# display.net
KiCad netlist of a schematic drawn in EAGLE
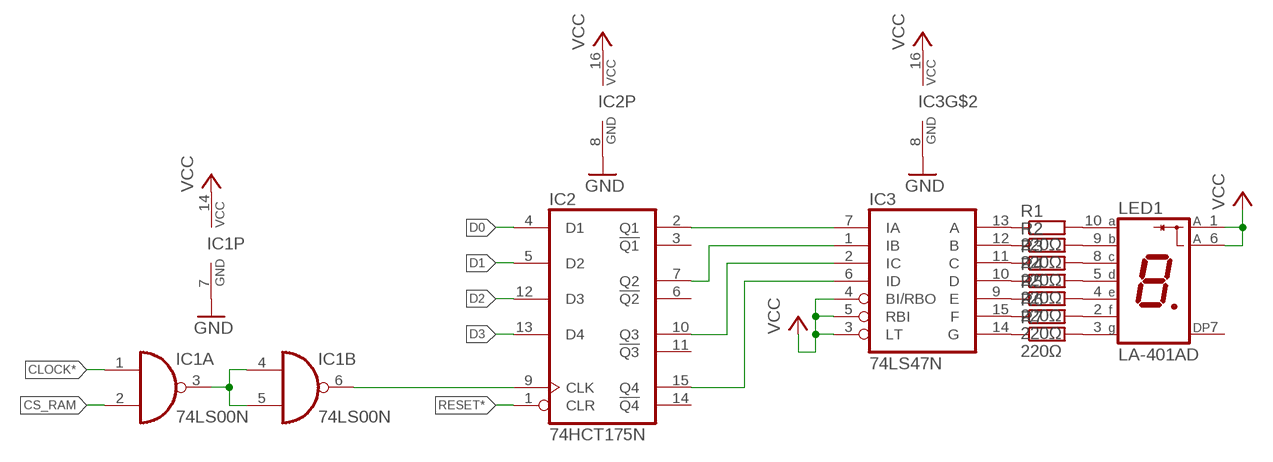
[diagram p0: schematic, sheet 1]

(export (version "E")
  (design (tool "Eeschema 10.0.6"))
  (components
    (comp (ref "IC1")
      (value "74LS00N")
      (footprint "eagle-import:DIL14")
      (libsource (lib "eagle-import") (part "7400NLS"))
    )
    (comp (ref "IC2")
      (value "74HCT175N")
      (footprint "eagle-import:DIL16")
      (libsource (lib "eagle-import") (part "74175NHCT"))
    )
    (comp (ref "IC3")
      (value "74LS47N")
      (footprint "eagle-import:DIL16")
      (libsource (lib "eagle-import") (part "7447NLS"))
    )
    (comp (ref "LED1")
      (value "LA-401AD")
      (footprint "eagle-import:LA-401")
      (libsource (lib "eagle-import") (part "LA-401DA"))
    )
    (comp (ref "R1")
      (value "220Ω")
      (footprint "eagle-import:0207_10")
      (libsource (lib "eagle-import") (part "R-EU_0207/10"))
    )
    (comp (ref "R2")
      (value "220Ω")
      (footprint "eagle-import:0207_10")
      (libsource (lib "eagle-import") (part "R-EU_0207/10"))
    )
    (comp (ref "R3")
      (value "220Ω")
      (footprint "eagle-import:0207_10")
      (libsource (lib "eagle-import") (part "R-EU_0207/10"))
    )
    (comp (ref "R4")
      (value "220Ω")
      (footprint "eagle-import:0207_10")
      (libsource (lib "eagle-import") (part "R-EU_0207/10"))
    )
    (comp (ref "R5")
      (value "220Ω")
      (footprint "eagle-import:0207_10")
      (libsource (lib "eagle-import") (part "R-EU_0207/10"))
    )
    (comp (ref "R6")
      (value "220Ω")
      (footprint "eagle-import:0207_10")
      (libsource (lib "eagle-import") (part "R-EU_0207/10"))
    )
    (comp (ref "R7")
      (value "220Ω")
      (footprint "eagle-import:0207_10")
      (libsource (lib "eagle-import") (part "R-EU_0207/10"))
    )
  )
  (nets
    (net (code "1") (name "CLOCK*") (class "Default")
      (node (ref "IC1") (pin "1") (pinfunction "I0_1") (pintype "input"))
    )
    (net (code "2") (name "CS_RAM") (class "Default")
      (node (ref "IC1") (pin "2") (pinfunction "I1_2") (pintype "input"))
    )
    (net (code "3") (name "D0") (class "Default")
      (node (ref "IC2") (pin "4") (pinfunction "D1_4") (pintype "input"))
    )
    (net (code "4") (name "D1") (class "Default")
      (node (ref "IC2") (pin "5") (pinfunction "D2_5") (pintype "input"))
    )
    (net (code "5") (name "D2") (class "Default")
      (node (ref "IC2") (pin "12") (pinfunction "D3_12") (pintype "input"))
    )
    (net (code "6") (name "D3") (class "Default")
      (node (ref "IC2") (pin "13") (pinfunction "D4_13") (pintype "input"))
    )
    (net (code "7") (name "GND") (class "Default")
      (node (ref "IC1") (pin "7") (pinfunction "GND_7") (pintype "power_in"))
      (node (ref "IC2") (pin "8") (pinfunction "GND_8") (pintype "power_in"))
      (node (ref "IC3") (pin "8") (pinfunction "GND_8") (pintype "power_in"))
    )
    (net (code "8") (name "Net-(IC1A-O)") (class "Default")
      (node (ref "IC1") (pin "3") (pinfunction "O_3") (pintype "output"))
      (node (ref "IC1") (pin "4") (pinfunction "I0_4") (pintype "input"))
      (node (ref "IC1") (pin "5") (pinfunction "I1_5") (pintype "input"))
    )
    (net (code "9") (name "Net-(IC1B-O)") (class "Default")
      (node (ref "IC1") (pin "6") (pinfunction "O_6") (pintype "output"))
      (node (ref "IC2") (pin "9") (pinfunction "CLK_9") (pintype "input"))
    )
    (net (code "10") (name "Net-(IC2A-Q1)") (class "Default")
      (node (ref "IC2") (pin "2") (pinfunction "Q1_2") (pintype "output"))
      (node (ref "IC3") (pin "7") (pinfunction "IA_7") (pintype "input"))
    )
    (net (code "11") (name "Net-(IC2A-Q2)") (class "Default")
      (node (ref "IC2") (pin "7") (pinfunction "Q2_7") (pintype "output"))
      (node (ref "IC3") (pin "1") (pinfunction "IB_1") (pintype "input"))
    )
    (net (code "12") (name "Net-(IC2A-Q3)") (class "Default")
      (node (ref "IC2") (pin "10") (pinfunction "Q3_10") (pintype "output"))
      (node (ref "IC3") (pin "2") (pinfunction "IC_2") (pintype "input"))
    )
    (net (code "13") (name "Net-(IC2A-Q4)") (class "Default")
      (node (ref "IC2") (pin "15") (pinfunction "Q4_15") (pintype "output"))
      (node (ref "IC3") (pin "6") (pinfunction "ID_6") (pintype "input"))
    )
    (net (code "14") (name "Net-(IC3A-A)") (class "Default")
      (node (ref "IC3") (pin "13") (pinfunction "A_13") (pintype "output"))
      (node (ref "R1") (pin "1") (pinfunction "1_1") (pintype "passive"))
    )
    (net (code "15") (name "Net-(IC3A-B)") (class "Default")
      (node (ref "IC3") (pin "12") (pinfunction "B_12") (pintype "output"))
      (node (ref "R2") (pin "1") (pinfunction "1_1") (pintype "passive"))
    )
    (net (code "16") (name "Net-(IC3A-C)") (class "Default")
      (node (ref "IC3") (pin "11") (pinfunction "C_11") (pintype "output"))
      (node (ref "R3") (pin "1") (pinfunction "1_1") (pintype "passive"))
    )
    (net (code "17") (name "Net-(IC3A-D)") (class "Default")
      (node (ref "IC3") (pin "10") (pinfunction "D_10") (pintype "output"))
      (node (ref "R4") (pin "1") (pinfunction "1_1") (pintype "passive"))
    )
    (net (code "18") (name "Net-(IC3A-E)") (class "Default")
      (node (ref "IC3") (pin "9") (pinfunction "E_9") (pintype "output"))
      (node (ref "R5") (pin "1") (pinfunction "1_1") (pintype "passive"))
    )
    (net (code "19") (name "Net-(IC3A-F)") (class "Default")
      (node (ref "IC3") (pin "15") (pinfunction "F_15") (pintype "output"))
      (node (ref "R6") (pin "1") (pinfunction "1_1") (pintype "passive"))
    )
    (net (code "20") (name "Net-(IC3A-G)") (class "Default")
      (node (ref "IC3") (pin "14") (pinfunction "G_14") (pintype "output"))
      (node (ref "R7") (pin "1") (pinfunction "1_1") (pintype "passive"))
    )
    (net (code "21") (name "Net-(LED1-A-Pad10)") (class "Default")
      (node (ref "LED1") (pin "10") (pinfunction "A_10") (pintype "passive"))
      (node (ref "R1") (pin "2") (pinfunction "2_2") (pintype "passive"))
    )
    (net (code "22") (name "Net-(LED1-B)") (class "Default")
      (node (ref "LED1") (pin "9") (pinfunction "B_9") (pintype "passive"))
      (node (ref "R2") (pin "2") (pinfunction "2_2") (pintype "passive"))
    )
    (net (code "23") (name "Net-(LED1-C)") (class "Default")
      (node (ref "LED1") (pin "8") (pinfunction "C_8") (pintype "passive"))
      (node (ref "R3") (pin "2") (pinfunction "2_2") (pintype "passive"))
    )
    (net (code "24") (name "Net-(LED1-D)") (class "Default")
      (node (ref "LED1") (pin "5") (pinfunction "D_5") (pintype "passive"))
      (node (ref "R4") (pin "2") (pinfunction "2_2") (pintype "passive"))
    )
    (net (code "25") (name "Net-(LED1-E)") (class "Default")
      (node (ref "LED1") (pin "4") (pinfunction "E_4") (pintype "passive"))
      (node (ref "R5") (pin "2") (pinfunction "2_2") (pintype "passive"))
    )
    (net (code "26") (name "Net-(LED1-F)") (class "Default")
      (node (ref "LED1") (pin "2") (pinfunction "F_2") (pintype "passive"))
      (node (ref "R6") (pin "2") (pinfunction "2_2") (pintype "passive"))
    )
    (net (code "27") (name "Net-(LED1-G)") (class "Default")
      (node (ref "LED1") (pin "3") (pinfunction "G_3") (pintype "passive"))
      (node (ref "R7") (pin "2") (pinfunction "2_2") (pintype "passive"))
    )
    (net (code "28") (name "RESET*") (class "Default")
      (node (ref "IC2") (pin "1") (pinfunction "CLR_1") (pintype "input"))
    )
    (net (code "29") (name "VCC") (class "Default")
      (node (ref "IC1") (pin "14") (pinfunction "VCC_14") (pintype "power_in"))
      (node (ref "IC2") (pin "16") (pinfunction "VCC_16") (pintype "power_in"))
      (node (ref "IC3") (pin "16") (pinfunction "VCC_16") (pintype "power_in"))
      (node (ref "IC3") (pin "3") (pinfunction "LT_3") (pintype "input"))
      (node (ref "IC3") (pin "4") (pinfunction "BI/RBO_4") (pintype "input"))
      (node (ref "IC3") (pin "5") (pinfunction "RBI_5") (pintype "input"))
      (node (ref "LED1") (pin "1") (pinfunction "A_1") (pintype "passive"))
      (node (ref "LED1") (pin "6") (pinfunction "A_6") (pintype "passive"))
    )
    (net (code "30") (name "unconnected-(IC2A-~{Q1}-Pad3)") (class "Default")
      (node (ref "IC2") (pin "3") (pinfunction "~{Q1}_3") (pintype "output"))
    )
    (net (code "31") (name "unconnected-(IC2A-~{Q2}-Pad6)") (class "Default")
      (node (ref "IC2") (pin "6") (pinfunction "~{Q2}_6") (pintype "output"))
    )
    (net (code "32") (name "unconnected-(IC2A-~{Q3}-Pad11)") (class "Default")
      (node (ref "IC2") (pin "11") (pinfunction "~{Q3}_11") (pintype "output"))
    )
    (net (code "33") (name "unconnected-(IC2A-~{Q4}-Pad14)") (class "Default")
      (node (ref "IC2") (pin "14") (pinfunction "~{Q4}_14") (pintype "output"))
    )
    (net (code "34") (name "unconnected-(LED1-DP-Pad7)") (class "Default")
      (node (ref "LED1") (pin "7") (pinfunction "DP_7") (pintype "passive"))
    )
  )
)
